# untitled.net
KiCad netlist of a schematic drawn in EAGLE
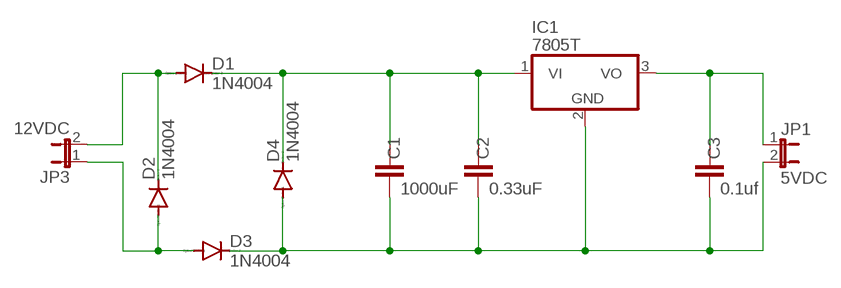
[diagram p0: schematic, sheet 1]

(export (version "E")
  (design (tool "Eeschema 10.0.6"))
  (components
    (comp (ref "C1")
      (value "1000uF")
      (footprint "eagle-import:C2.5-3")
      (libsource (lib "eagle-import") (part "C2,5-3"))
    )
    (comp (ref "C2")
      (value "0.33uF")
      (footprint "eagle-import:C2.5-3")
      (libsource (lib "eagle-import") (part "C2,5-3"))
    )
    (comp (ref "C3")
      (value "0.1uf")
      (footprint "eagle-import:C2.5-3")
      (libsource (lib "eagle-import") (part "C2,5-3"))
    )
    (comp (ref "D1")
      (value "1N4004")
      (footprint "eagle-import:DO41-10")
      (libsource (lib "eagle-import") (part "1N4004"))
    )
    (comp (ref "D2")
      (value "1N4004")
      (footprint "eagle-import:DO41-10")
      (libsource (lib "eagle-import") (part "1N4004"))
    )
    (comp (ref "D3")
      (value "1N4004")
      (footprint "eagle-import:DO41-10")
      (libsource (lib "eagle-import") (part "1N4004"))
    )
    (comp (ref "D4")
      (value "1N4004")
      (footprint "eagle-import:DO41-10")
      (libsource (lib "eagle-import") (part "1N4004"))
    )
    (comp (ref "IC1")
      (value "7805T")
      (footprint "eagle-import:TO220H")
      (libsource (lib "eagle-import") (part "78T05"))
    )
    (comp (ref "JP1")
      (value "5VDC")
      (footprint "eagle-import:JP1")
      (libsource (lib "eagle-import") (part "JP1E"))
    )
    (comp (ref "JP3")
      (value "12VDC")
      (footprint "eagle-import:JP1")
      (libsource (lib "eagle-import") (part "JP1E"))
    )
  )
  (nets
    (net (code "1") (name "Net-(D1-PadA)") (class "Default")
      (node (ref "D1") (pin "A") (pinfunction "A_A") (pintype "passive"))
      (node (ref "D2") (pin "C") (pinfunction "C_C") (pintype "passive"))
      (node (ref "JP3") (pin "2") (pinfunction "2_2") (pintype "passive"))
    )
    (net (code "2") (name "Net-(D2-PadA)") (class "Default")
      (node (ref "D2") (pin "A") (pinfunction "A_A") (pintype "passive"))
      (node (ref "D3") (pin "A") (pinfunction "A_A") (pintype "passive"))
      (node (ref "JP3") (pin "1") (pinfunction "1_1") (pintype "passive"))
    )
    (net (code "3") (name "Net-(IC1-GND)") (class "Default")
      (node (ref "C1") (pin "2") (pinfunction "2_2") (pintype "passive"))
      (node (ref "C2") (pin "2") (pinfunction "2_2") (pintype "passive"))
      (node (ref "C3") (pin "2") (pinfunction "2_2") (pintype "passive"))
      (node (ref "D3") (pin "C") (pinfunction "C_C") (pintype "passive"))
      (node (ref "D4") (pin "A") (pinfunction "A_A") (pintype "passive"))
      (node (ref "IC1") (pin "2") (pinfunction "GND_2") (pintype "passive"))
      (node (ref "JP1") (pin "2") (pinfunction "2_2") (pintype "passive"))
    )
    (net (code "4") (name "Net-(IC1-VI)") (class "Default")
      (node (ref "C1") (pin "1") (pinfunction "1_1") (pintype "passive"))
      (node (ref "C2") (pin "1") (pinfunction "1_1") (pintype "passive"))
      (node (ref "D1") (pin "C") (pinfunction "C_C") (pintype "passive"))
      (node (ref "D4") (pin "C") (pinfunction "C_C") (pintype "passive"))
      (node (ref "IC1") (pin "1") (pinfunction "VI_1") (pintype "input"))
    )
    (net (code "5") (name "Net-(IC1-VO)") (class "Default")
      (node (ref "C3") (pin "1") (pinfunction "1_1") (pintype "passive"))
      (node (ref "IC1") (pin "3") (pinfunction "VO_3") (pintype "passive"))
      (node (ref "JP1") (pin "1") (pinfunction "1_1") (pintype "passive"))
    )
  )
)
